# lvc.net
KiCad netlist of a schematic drawn in EAGLE
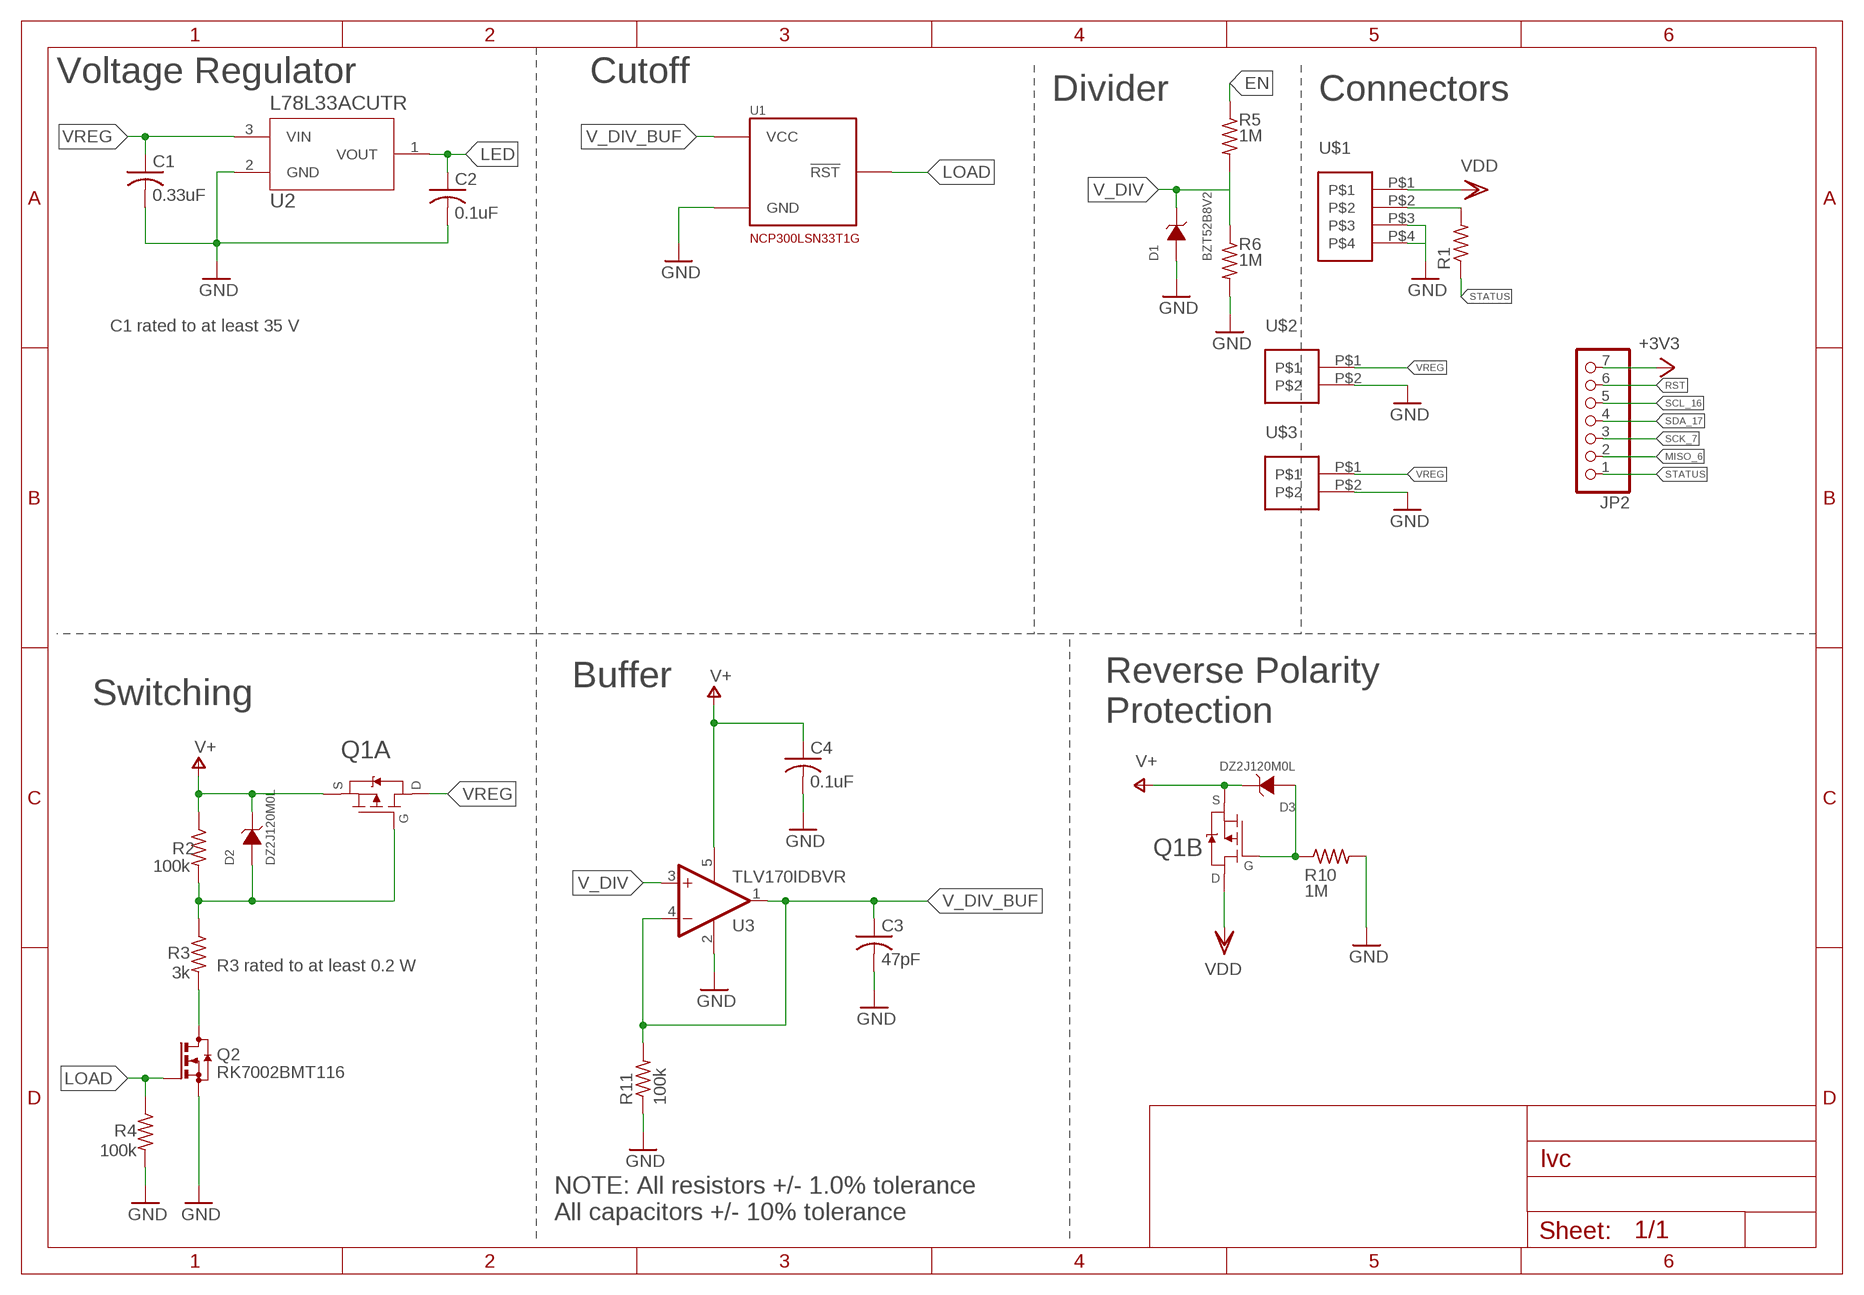
[diagram p0: schematic, sheet 1]

(export (version "E")
  (design (tool "Eeschema 10.0.6"))
  (components
    (comp (ref "C1")
      (value "0.33uF")
      (footprint "eagle-import:C0603")
      (libsource (lib "eagle-import") (part "C-USC0603"))
    )
    (comp (ref "C2")
      (value "0.1uF")
      (footprint "eagle-import:C0603")
      (libsource (lib "eagle-import") (part "C-USC0603"))
    )
    (comp (ref "C3")
      (value "47pF")
      (footprint "eagle-import:C0603")
      (libsource (lib "eagle-import") (part "C-USC0603"))
    )
    (comp (ref "C4")
      (value "0.1uF")
      (footprint "eagle-import:C0603")
      (libsource (lib "eagle-import") (part "C-USC0603"))
    )
    (comp (ref "D1")
      (value "BZT52B8V2")
      (footprint "eagle-import:SOD123")
      (libsource (lib "eagle-import") (part "BZT52B8V2"))
    )
    (comp (ref "D2")
      (value "DZ2J120M0L")
      (footprint "eagle-import:SMINI2-F5-B")
      (libsource (lib "eagle-import") (part "DZ2J120M0L"))
    )
    (comp (ref "D3")
      (value "DZ2J120M0L")
      (footprint "eagle-import:SMINI2-F5-B")
      (libsource (lib "eagle-import") (part "DZ2J120M0L"))
    )
    (comp (ref "JP2")
      (value "PINHD-1X7")
      (footprint "eagle-import:1X07")
      (libsource (lib "eagle-import") (part "PINHD-1X7"))
    )
    (comp (ref "Q1")
      (value "SI7997DP")
      (footprint "eagle-import:POWERPAK-SO-8-DUAL")
      (libsource (lib "eagle-import") (part "SI7997DP"))
    )
    (comp (ref "Q2")
      (value "RK7002BMT116")
      (footprint "eagle-import:SOT23")
      (libsource (lib "eagle-import") (part "RK7002BMT116"))
    )
    (comp (ref "R1")
      (value "R-US_R0603")
      (footprint "eagle-import:R0603")
      (libsource (lib "eagle-import") (part "resistor_R-US_R0603"))
    )
    (comp (ref "R2")
      (value "100k")
      (footprint "eagle-import:R0603")
      (libsource (lib "eagle-import") (part "resistor_R-US_R0603"))
    )
    (comp (ref "R3")
      (value "3k")
      (footprint "eagle-import:R0603")
      (libsource (lib "eagle-import") (part "resistor_R-US_R0603"))
    )
    (comp (ref "R4")
      (value "100k")
      (footprint "eagle-import:R0603")
      (libsource (lib "eagle-import") (part "resistor_R-US_R0603"))
    )
    (comp (ref "R5")
      (value "1M")
      (footprint "eagle-import:R0603")
      (libsource (lib "eagle-import") (part "resistor_R-US_R0603"))
    )
    (comp (ref "R6")
      (value "1M")
      (footprint "eagle-import:R0603")
      (libsource (lib "eagle-import") (part "resistor_R-US_R0603"))
    )
    (comp (ref "R10")
      (value "1M")
      (footprint "eagle-import:R0603")
      (libsource (lib "eagle-import") (part "resistor_R-US_R0603"))
    )
    (comp (ref "R11")
      (value "100k")
      (footprint "eagle-import:R0603")
      (libsource (lib "eagle-import") (part "R-US_R0603"))
    )
    (comp (ref "U$1")
      (value "MICROCLASP_4")
      (footprint "eagle-import:4_PIN_MICROCLASP")
      (libsource (lib "eagle-import") (part "MICROCLASP_4"))
    )
    (comp (ref "U$2")
      (value "LITEAPRS")
      (footprint "eagle-import:LITEAPRS")
      (libsource (lib "eagle-import") (part "LITEAPRS"))
    )
    (comp (ref "U$3")
      (value "LITEAPRS")
      (footprint "eagle-import:LITEAPRS")
      (libsource (lib "eagle-import") (part "LITEAPRS"))
    )
    (comp (ref "U1")
      (value "NCP300LSN33T1G")
      (footprint "eagle-import:SOT23-5")
      (libsource (lib "eagle-import") (part "NCP300LSN33T1G"))
    )
    (comp (ref "U2")
      (value "L78L33ACUTR")
      (footprint "eagle-import:SOT-89")
      (libsource (lib "eagle-import") (part "L78L33ACUTR"))
    )
    (comp (ref "U3")
      (value "TLV170IDBVR")
      (footprint "eagle-import:SOT23-DBV")
      (libsource (lib "eagle-import") (part "TLV170IDBVR"))
    )
  )
  (nets
    (net (code "1") (name "+3V3") (class "Default")
      (node (ref "JP2") (pin "7") (pinfunction "7_7") (pintype "passive"))
    )
    (net (code "2") (name "EN") (class "Default")
      (node (ref "R5") (pin "1") (pinfunction "1_1") (pintype "passive"))
    )
    (net (code "3") (name "GND") (class "Default")
      (node (ref "C1") (pin "2") (pinfunction "2_2") (pintype "passive"))
      (node (ref "C2") (pin "2") (pinfunction "2_2") (pintype "passive"))
      (node (ref "C3") (pin "2") (pinfunction "2_2") (pintype "passive"))
      (node (ref "C4") (pin "2") (pinfunction "2_2") (pintype "passive"))
      (node (ref "D1") (pin "A") (pinfunction "A_A") (pintype "bidirectional"))
      (node (ref "Q2") (pin "2") (pinfunction "S_2") (pintype "passive"))
      (node (ref "R10") (pin "2") (pinfunction "2_2") (pintype "passive"))
      (node (ref "R11") (pin "1") (pinfunction "1_1") (pintype "passive"))
      (node (ref "R4") (pin "2") (pinfunction "2_2") (pintype "passive"))
      (node (ref "R6") (pin "2") (pinfunction "2_2") (pintype "passive"))
      (node (ref "U$1") (pin "P$3") (pinfunction "P$3_P$3") (pintype "bidirectional"))
      (node (ref "U$1") (pin "P$4") (pinfunction "P$4_P$4") (pintype "bidirectional"))
      (node (ref "U$2") (pin "P$2") (pinfunction "P$2_P$2") (pintype "bidirectional"))
      (node (ref "U$3") (pin "P$2") (pinfunction "P$2_P$2") (pintype "bidirectional"))
      (node (ref "U1") (pin "3") (pinfunction "GND_3") (pintype "power_in"))
      (node (ref "U2") (pin "2") (pinfunction "GND_2") (pintype "passive"))
      (node (ref "U3") (pin "2") (pinfunction "V-_2") (pintype "power_in"))
    )
    (net (code "4") (name "LED") (class "Default")
      (node (ref "C2") (pin "1") (pinfunction "1_1") (pintype "passive"))
      (node (ref "U2") (pin "1") (pinfunction "VOUT_1") (pintype "output"))
    )
    (net (code "5") (name "LOAD") (class "Default")
      (node (ref "Q2") (pin "1") (pinfunction "G_1") (pintype "passive"))
      (node (ref "R4") (pin "1") (pinfunction "1_1") (pintype "passive"))
      (node (ref "U1") (pin "1") (pinfunction "~{RST}_1") (pintype "bidirectional"))
    )
    (net (code "6") (name "MISO_6") (class "Default")
      (node (ref "JP2") (pin "2") (pinfunction "2_2") (pintype "passive"))
    )
    (net (code "7") (name "Net-(Q1A-G)") (class "Default")
      (node (ref "D2") (pin "A") (pinfunction "A_A") (pintype "passive"))
      (node (ref "Q1") (pin "4") (pinfunction "G_4") (pintype "bidirectional"))
      (node (ref "R2") (pin "2") (pinfunction "2_2") (pintype "passive"))
      (node (ref "R3") (pin "1") (pinfunction "1_1") (pintype "passive"))
    )
    (net (code "8") (name "Net-(Q1B-G)") (class "Default")
      (node (ref "D3") (pin "A") (pinfunction "A_A") (pintype "passive"))
      (node (ref "Q1") (pin "2") (pinfunction "G_2") (pintype "bidirectional"))
      (node (ref "R10") (pin "1") (pinfunction "1_1") (pintype "passive"))
    )
    (net (code "9") (name "Net-(Q2-D)") (class "Default")
      (node (ref "Q2") (pin "3") (pinfunction "D_3") (pintype "passive"))
      (node (ref "R3") (pin "2") (pinfunction "2_2") (pintype "passive"))
    )
    (net (code "10") (name "Net-(R1-Pad2)") (class "Default")
      (node (ref "R1") (pin "2") (pinfunction "2_2") (pintype "passive"))
      (node (ref "U$1") (pin "P$2") (pinfunction "P$2_P$2") (pintype "bidirectional"))
    )
    (net (code "11") (name "RST") (class "Default")
      (node (ref "JP2") (pin "6") (pinfunction "6_6") (pintype "passive"))
    )
    (net (code "12") (name "SCK_7") (class "Default")
      (node (ref "JP2") (pin "3") (pinfunction "3_3") (pintype "passive"))
    )
    (net (code "13") (name "SCL_16") (class "Default")
      (node (ref "JP2") (pin "5") (pinfunction "5_5") (pintype "passive"))
    )
    (net (code "14") (name "SDA_17") (class "Default")
      (node (ref "JP2") (pin "4") (pinfunction "4_4") (pintype "passive"))
    )
    (net (code "15") (name "STATUS") (class "Default")
      (node (ref "JP2") (pin "1") (pinfunction "1_1") (pintype "passive"))
      (node (ref "R1") (pin "1") (pinfunction "1_1") (pintype "passive"))
    )
    (net (code "16") (name "V+") (class "Default")
      (node (ref "C4") (pin "1") (pinfunction "1_1") (pintype "passive"))
      (node (ref "D2") (pin "C") (pinfunction "C_C") (pintype "passive"))
      (node (ref "D3") (pin "C") (pinfunction "C_C") (pintype "passive"))
      (node (ref "Q1") (pin "1") (pinfunction "S_1") (pintype "bidirectional"))
      (node (ref "Q1") (pin "3") (pinfunction "S_3") (pintype "bidirectional"))
      (node (ref "R2") (pin "1") (pinfunction "1_1") (pintype "passive"))
      (node (ref "U3") (pin "5") (pinfunction "V+_5") (pintype "power_in"))
    )
    (net (code "17") (name "VDD") (class "Default")
      (node (ref "Q1") (pin "7") (pinfunction "D_7") (pintype "bidirectional"))
      (node (ref "Q1") (pin "8") (pinfunction "D_8") (pintype "bidirectional"))
      (node (ref "Q1") (pin "8L") (pinfunction "D_8L") (pintype "bidirectional"))
      (node (ref "U$1") (pin "P$1") (pinfunction "P$1_P$1") (pintype "bidirectional"))
    )
    (net (code "18") (name "VREG") (class "Default")
      (node (ref "C1") (pin "1") (pinfunction "1_1") (pintype "passive"))
      (node (ref "Q1") (pin "5") (pinfunction "D_5") (pintype "bidirectional"))
      (node (ref "Q1") (pin "5L") (pinfunction "D_5L") (pintype "bidirectional"))
      (node (ref "Q1") (pin "6") (pinfunction "D_6") (pintype "bidirectional"))
      (node (ref "U$2") (pin "P$1") (pinfunction "P$1_P$1") (pintype "bidirectional"))
      (node (ref "U$3") (pin "P$1") (pinfunction "P$1_P$1") (pintype "bidirectional"))
      (node (ref "U2") (pin "3") (pinfunction "VIN_3") (pintype "input"))
    )
    (net (code "19") (name "V_DIV") (class "Default")
      (node (ref "D1") (pin "C") (pinfunction "C_C") (pintype "bidirectional"))
      (node (ref "R5") (pin "2") (pinfunction "2_2") (pintype "passive"))
      (node (ref "R6") (pin "1") (pinfunction "1_1") (pintype "passive"))
      (node (ref "U3") (pin "3") (pinfunction "+IN_3") (pintype "input"))
    )
    (net (code "20") (name "V_DIV_BUF") (class "Default")
      (node (ref "C3") (pin "1") (pinfunction "1_1") (pintype "passive"))
      (node (ref "R11") (pin "2") (pinfunction "2_2") (pintype "passive"))
      (node (ref "U1") (pin "2") (pinfunction "VCC_2") (pintype "power_in"))
      (node (ref "U3") (pin "1") (pinfunction "OUT_1") (pintype "output"))
      (node (ref "U3") (pin "4") (pinfunction "-IN_4") (pintype "input"))
    )
  )
)
